# PLL.net
KiCad netlist of a schematic drawn in Altium Designer
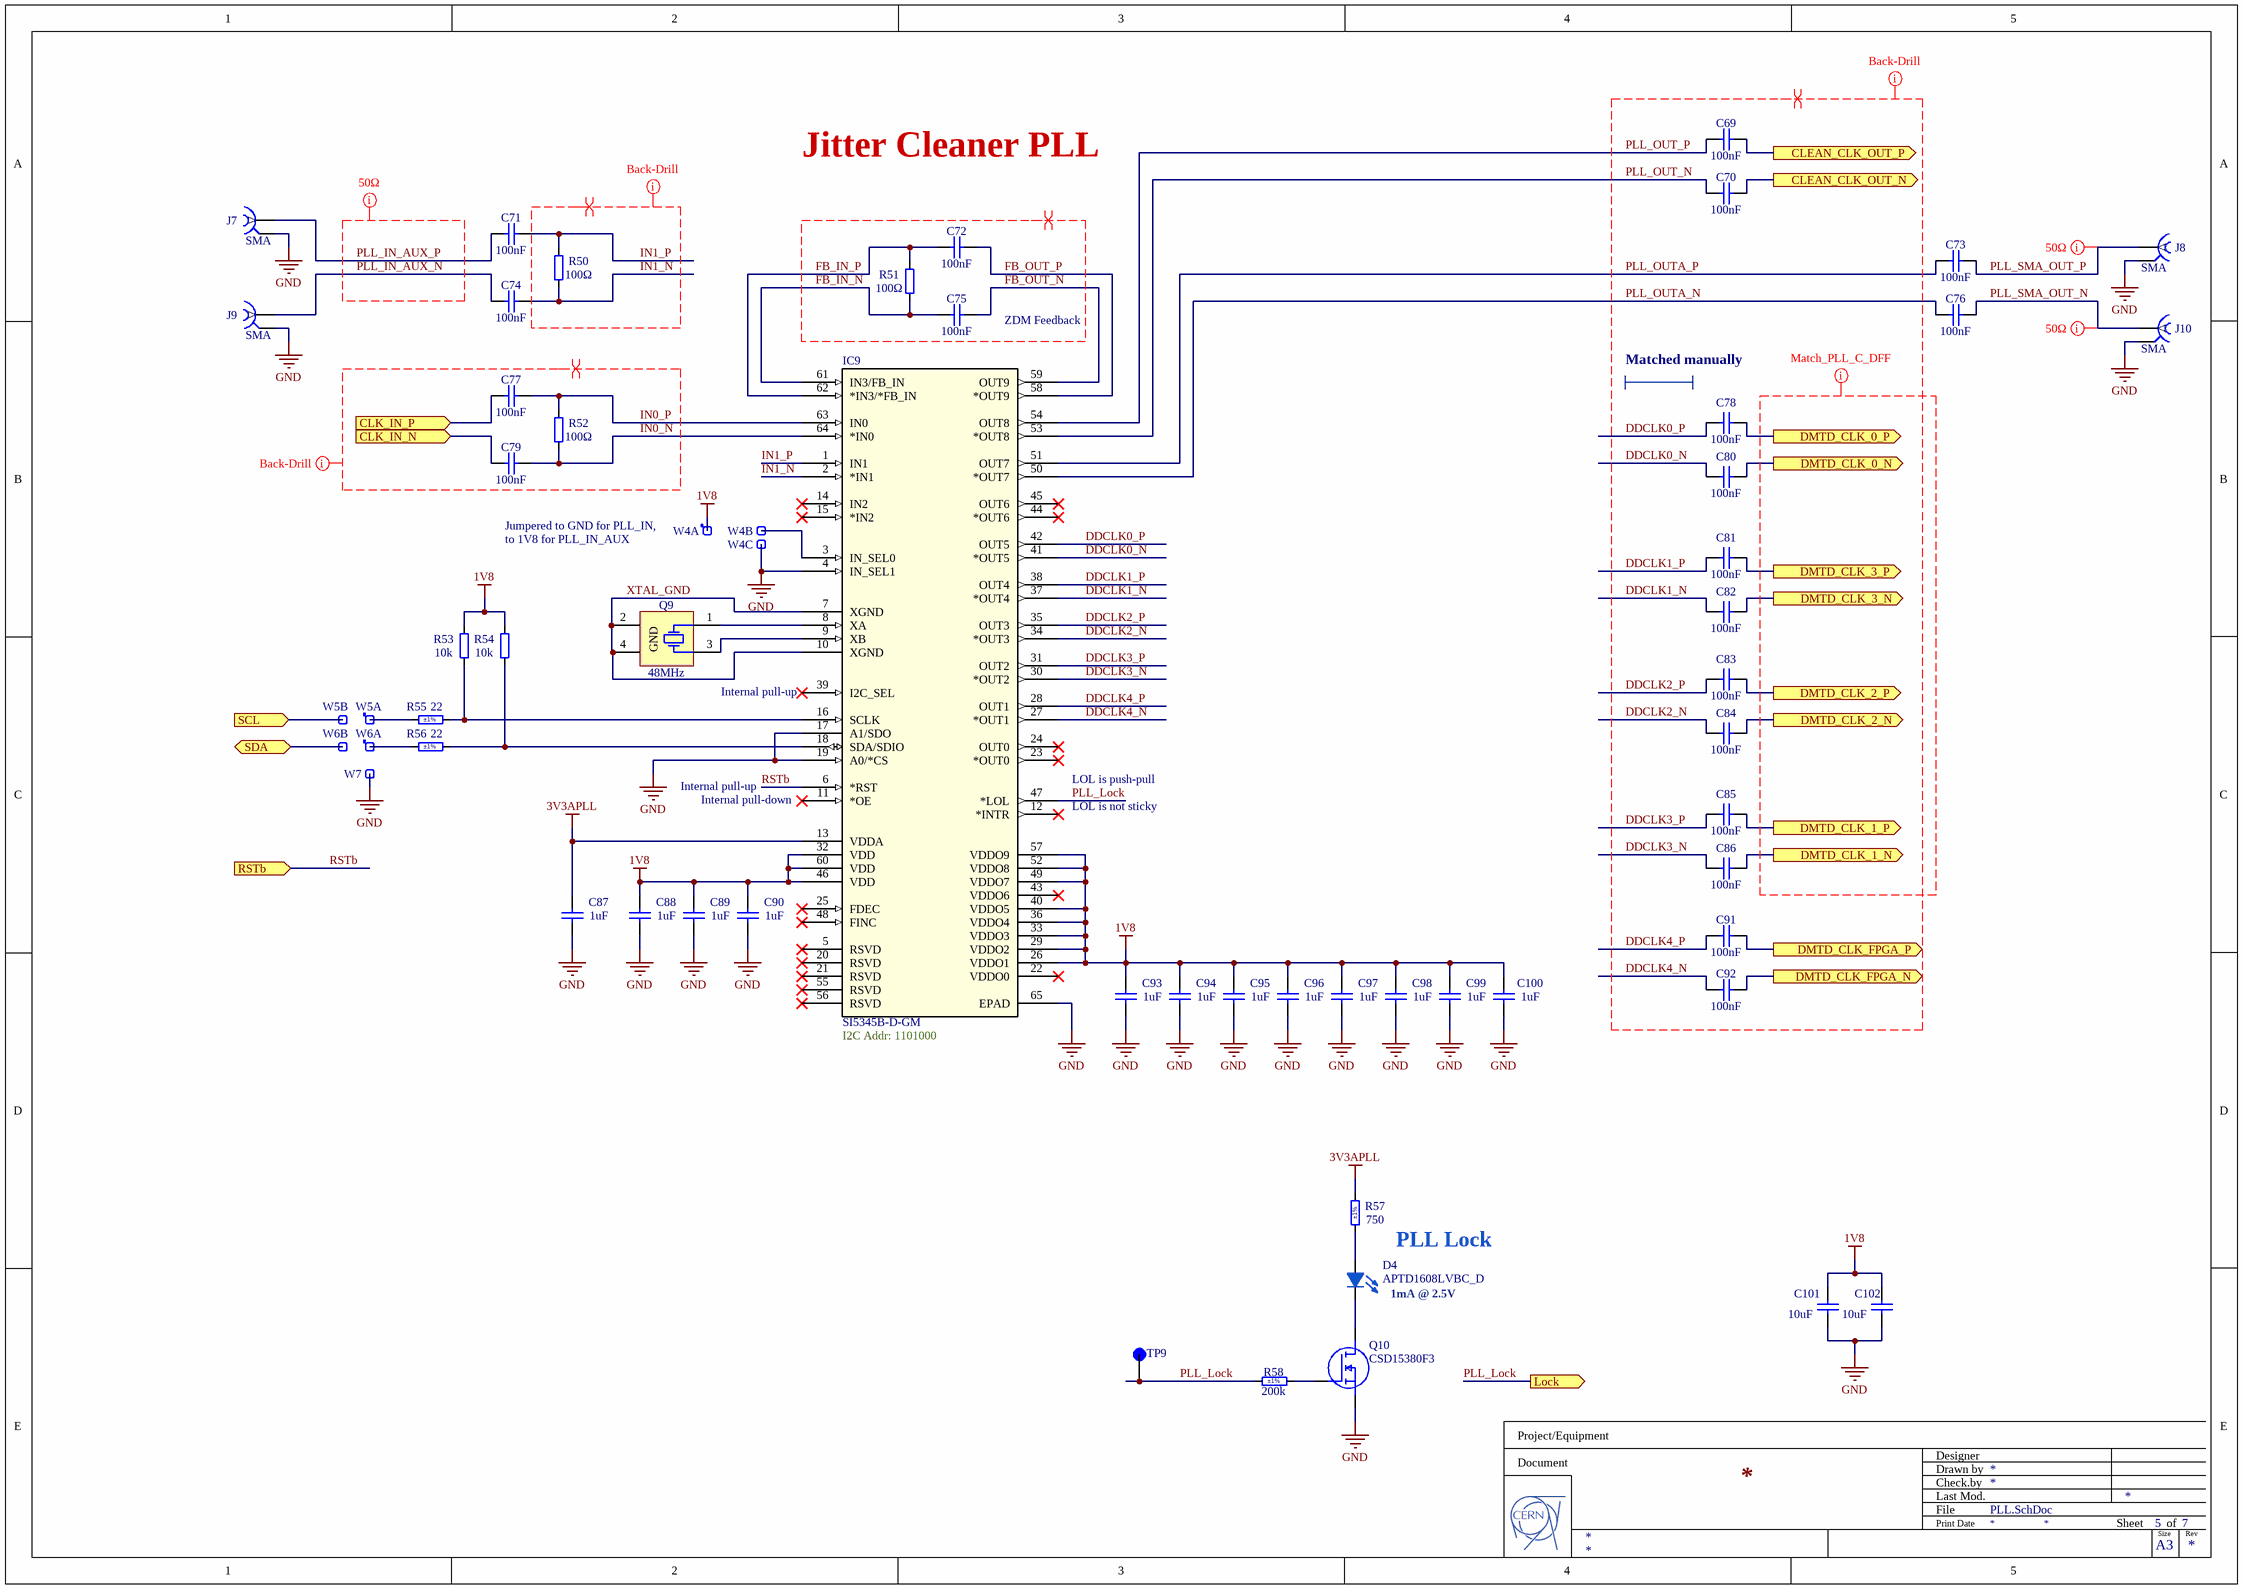
[diagram p0: PLL.SchDoc]

(export (version "E")
  (design (tool "Eeschema 10.0.6"))
  (components
    (comp (ref "C69")
      (value "100nF")
      (footprint "MURATA_HI_DENSITY_0201")
      (description "GRM033R61C104KE14")
      (libsource (lib "schLib") (part "C0201-100nF-high-density"))
    )
    (comp (ref "C70")
      (value "100nF")
      (footprint "MURATA_HI_DENSITY_0201")
      (description "GRM033R61C104KE14")
      (libsource (lib "schLib") (part "C0201-100nF-high-density"))
    )
    (comp (ref "C71")
      (value "100nF")
      (footprint "MURATA_HI_DENSITY_0201")
      (description "GRM033R61C104KE14")
      (libsource (lib "schLib") (part "C0201-100nF-high-density"))
    )
    (comp (ref "C72")
      (value "100nF")
      (footprint "MURATA_HI_DENSITY_0201")
      (description "GRM033R61C104KE14")
      (libsource (lib "schLib") (part "C0201-100nF-high-density"))
    )
    (comp (ref "C73")
      (value "100nF")
      (footprint "MURATA_HI_DENSITY_0201")
      (description "GRM033R61C104KE14")
      (libsource (lib "schLib") (part "C0201-100nF-high-density"))
    )
    (comp (ref "C74")
      (value "100nF")
      (footprint "MURATA_HI_DENSITY_0201")
      (description "GRM033R61C104KE14")
      (libsource (lib "schLib") (part "C0201-100nF-high-density"))
    )
    (comp (ref "C75")
      (value "100nF")
      (footprint "MURATA_HI_DENSITY_0201")
      (description "GRM033R61C104KE14")
      (libsource (lib "schLib") (part "C0201-100nF-high-density"))
    )
    (comp (ref "C76")
      (value "100nF")
      (footprint "MURATA_HI_DENSITY_0201")
      (description "GRM033R61C104KE14")
      (libsource (lib "schLib") (part "C0201-100nF-high-density"))
    )
    (comp (ref "C77")
      (value "100nF")
      (footprint "MURATA_HI_DENSITY_0201")
      (description "GRM033R61C104KE14")
      (libsource (lib "schLib") (part "C0201-100nF-high-density"))
    )
    (comp (ref "C78")
      (value "100nF")
      (footprint "MURATA_HI_DENSITY_0201")
      (description "GRM033R61C104KE14")
      (libsource (lib "schLib") (part "C0201-100nF-high-density"))
    )
    (comp (ref "C79")
      (value "100nF")
      (footprint "MURATA_HI_DENSITY_0201")
      (description "GRM033R61C104KE14")
      (libsource (lib "schLib") (part "C0201-100nF-high-density"))
    )
    (comp (ref "C80")
      (value "100nF")
      (footprint "MURATA_HI_DENSITY_0201")
      (description "GRM033R61C104KE14")
      (libsource (lib "schLib") (part "C0201-100nF-high-density"))
    )
    (comp (ref "C81")
      (value "100nF")
      (footprint "MURATA_HI_DENSITY_0201")
      (description "GRM033R61C104KE14")
      (libsource (lib "schLib") (part "C0201-100nF-high-density"))
    )
    (comp (ref "C82")
      (value "100nF")
      (footprint "MURATA_HI_DENSITY_0201")
      (description "GRM033R61C104KE14")
      (libsource (lib "schLib") (part "C0201-100nF-high-density"))
    )
    (comp (ref "C83")
      (value "100nF")
      (footprint "MURATA_HI_DENSITY_0201")
      (description "GRM033R61C104KE14")
      (libsource (lib "schLib") (part "C0201-100nF-high-density"))
    )
    (comp (ref "C84")
      (value "100nF")
      (footprint "MURATA_HI_DENSITY_0201")
      (description "GRM033R61C104KE14")
      (libsource (lib "schLib") (part "C0201-100nF-high-density"))
    )
    (comp (ref "C85")
      (value "100nF")
      (footprint "MURATA_HI_DENSITY_0201")
      (description "GRM033R61C104KE14")
      (libsource (lib "schLib") (part "C0201-100nF-high-density"))
    )
    (comp (ref "C86")
      (value "100nF")
      (footprint "MURATA_HI_DENSITY_0201")
      (description "GRM033R61C104KE14")
      (libsource (lib "schLib") (part "C0201-100nF-high-density"))
    )
    (comp (ref "C87")
      (value "1uF")
      (footprint "CAPC1005X55N")
      (description "GRM153B30J105ME15")
      (fields
        (field (name "PART NUMBER") "CC0402_1UF_16V_10%_X5R")
        (field (name "VOLTAGE") "16V")
        (field (name "AUTHOR") "CERN DEM JLC")
      )
      (libsource (lib "Capacitors") (part "Capacitor - non polarized"))
    )
    (comp (ref "C88")
      (value "1uF")
      (footprint "CAPC1005X55N")
      (description "GRM153B30J105ME15")
      (fields
        (field (name "PART NUMBER") "CC0402_1UF_16V_10%_X5R")
        (field (name "VOLTAGE") "16V")
        (field (name "AUTHOR") "CERN DEM JLC")
      )
      (libsource (lib "Capacitors") (part "Capacitor - non polarized"))
    )
    (comp (ref "C89")
      (value "1uF")
      (footprint "CAPC1005X55N")
      (description "GRM153B30J105ME15")
      (fields
        (field (name "PART NUMBER") "CC0402_1UF_16V_10%_X5R")
        (field (name "VOLTAGE") "16V")
        (field (name "AUTHOR") "CERN DEM JLC")
      )
      (libsource (lib "Capacitors") (part "Capacitor - non polarized"))
    )
    (comp (ref "C90")
      (value "1uF")
      (footprint "CAPC1005X55N")
      (description "GRM153B30J105ME15")
      (fields
        (field (name "PART NUMBER") "CC0402_1UF_16V_10%_X5R")
        (field (name "VOLTAGE") "16V")
        (field (name "AUTHOR") "CERN DEM JLC")
      )
      (libsource (lib "Capacitors") (part "Capacitor - non polarized"))
    )
    (comp (ref "C91")
      (value "100nF")
      (footprint "MURATA_HI_DENSITY_0201")
      (description "GRM033R61C104KE14")
      (libsource (lib "schLib") (part "C0201-100nF-high-density"))
    )
    (comp (ref "C92")
      (value "100nF")
      (footprint "MURATA_HI_DENSITY_0201")
      (description "GRM033R61C104KE14")
      (libsource (lib "schLib") (part "C0201-100nF-high-density"))
    )
    (comp (ref "C93")
      (value "1uF")
      (footprint "CAPC1005X55N")
      (description "GRM153B30J105ME15")
      (fields
        (field (name "PART NUMBER") "CC0402_1UF_16V_10%_X5R")
        (field (name "VOLTAGE") "16V")
        (field (name "AUTHOR") "CERN DEM JLC")
      )
      (libsource (lib "Capacitors") (part "Capacitor - non polarized"))
    )
    (comp (ref "C94")
      (value "1uF")
      (footprint "CAPC1005X55N")
      (description "GRM153B30J105ME15")
      (fields
        (field (name "PART NUMBER") "CC0402_1UF_16V_10%_X5R")
        (field (name "VOLTAGE") "16V")
        (field (name "AUTHOR") "CERN DEM JLC")
      )
      (libsource (lib "Capacitors") (part "Capacitor - non polarized"))
    )
    (comp (ref "C95")
      (value "1uF")
      (footprint "CAPC1005X55N")
      (description "GRM153B30J105ME15")
      (fields
        (field (name "PART NUMBER") "CC0402_1UF_16V_10%_X5R")
        (field (name "VOLTAGE") "16V")
        (field (name "AUTHOR") "CERN DEM JLC")
      )
      (libsource (lib "Capacitors") (part "Capacitor - non polarized"))
    )
    (comp (ref "C96")
      (value "1uF")
      (footprint "CAPC1005X55N")
      (description "GRM153B30J105ME15")
      (fields
        (field (name "PART NUMBER") "CC0402_1UF_16V_10%_X5R")
        (field (name "VOLTAGE") "16V")
        (field (name "AUTHOR") "CERN DEM JLC")
      )
      (libsource (lib "Capacitors") (part "Capacitor - non polarized"))
    )
    (comp (ref "C97")
      (value "1uF")
      (footprint "CAPC1005X55N")
      (description "GRM153B30J105ME15")
      (fields
        (field (name "PART NUMBER") "CC0402_1UF_16V_10%_X5R")
        (field (name "VOLTAGE") "16V")
        (field (name "AUTHOR") "CERN DEM JLC")
      )
      (libsource (lib "Capacitors") (part "Capacitor - non polarized"))
    )
    (comp (ref "C98")
      (value "1uF")
      (footprint "CAPC1005X55N")
      (description "GRM153B30J105ME15")
      (fields
        (field (name "PART NUMBER") "CC0402_1UF_16V_10%_X5R")
        (field (name "VOLTAGE") "16V")
        (field (name "AUTHOR") "CERN DEM JLC")
      )
      (libsource (lib "Capacitors") (part "Capacitor - non polarized"))
    )
    (comp (ref "C99")
      (value "1uF")
      (footprint "CAPC1005X55N")
      (description "GRM153B30J105ME15")
      (fields
        (field (name "PART NUMBER") "CC0402_1UF_16V_10%_X5R")
        (field (name "VOLTAGE") "16V")
        (field (name "AUTHOR") "CERN DEM JLC")
      )
      (libsource (lib "Capacitors") (part "Capacitor - non polarized"))
    )
    (comp (ref "C100")
      (value "1uF")
      (footprint "CAPC1005X55N")
      (description "GRM153B30J105ME15")
      (fields
        (field (name "PART NUMBER") "CC0402_1UF_16V_10%_X5R")
        (field (name "VOLTAGE") "16V")
        (field (name "AUTHOR") "CERN DEM JLC")
      )
      (libsource (lib "Capacitors") (part "Capacitor - non polarized"))
    )
    (comp (ref "C101")
      (value "10uF")
      (footprint "CAPC1608X87N")
      (description "C1608X5R1E106M080AC")
      (fields
        (field (name "PART NUMBER") "CC0603_10UF_6.3V_20%_X5R")
        (field (name "VOLTAGE") "6.3V")
        (field (name "AUTHOR") "CERN DEM JLC")
      )
      (libsource (lib "Capacitors") (part "Capacitor - non polarized"))
    )
    (comp (ref "C102")
      (value "10uF")
      (footprint "CAPC1608X87N")
      (description "C1608X5R1E106M080AC")
      (fields
        (field (name "PART NUMBER") "CC0603_10UF_6.3V_20%_X5R")
        (field (name "VOLTAGE") "6.3V")
        (field (name "AUTHOR") "CERN DEM JLC")
      )
      (libsource (lib "Capacitors") (part "Capacitor - non polarized"))
    )
    (comp (ref "D4")
      (value "APTD1608LVBC_D")
      (footprint "SamacSys:LEDC1608X110N")
      (description "LED")
      (fields
        (field (name "MANUFACTURER_PART_NUMBER") "APTD1608LVBC/D")
        (field (name "MOUSER PART NUMBER") "604-APTD1608LVBCD")
      )
      (libsource (lib "SamacSys") (part "APTD1608LVBC_D"))
    )
    (comp (ref "IC9")
      (value "SI5345B-D-GM")
      (footprint "SamacSys:QFN50P900X900X90-65N-D")
      (description "Integrated Circuit")
      (fields (field (name "MOUSER PART NUMBER") "634-SI5345B-D-GM"))
      (libsource (lib "SamacSys") (part "SI5345B-D-GM"))
    )
    (comp (ref "J7")
      (value "SMA")
      (footprint "SAMTEC_SMA-J-P-H-ST-MT1")
      (fields
        (field (name "PART NUMBER") "SAMTEC_SMA-J-P-H-ST-MT1")
        (field (name "MANUFACTURER") "SAMTEC")
        (field (name "MANUFACTURER PART NUMBER") "SMA-J-P-H-ST-MT1")
        (field (name "AUTHOR") "CERN DEM HF")
      )
      (libsource (lib "Connectors") (part "Coax_1Female_1Shield"))
    )
    (comp (ref "J8")
      (value "SMA")
      (footprint "SAMTEC_SMA-J-P-H-ST-MT1")
      (fields
        (field (name "PART NUMBER") "SAMTEC_SMA-J-P-H-ST-MT1")
        (field (name "MANUFACTURER") "SAMTEC")
        (field (name "MANUFACTURER PART NUMBER") "SMA-J-P-H-ST-MT1")
        (field (name "AUTHOR") "CERN DEM HF")
      )
      (libsource (lib "") (part "Coax_1Female_1Shield_1"))
    )
    (comp (ref "J9")
      (value "SMA")
      (footprint "SAMTEC_SMA-J-P-H-ST-MT1")
      (fields
        (field (name "PART NUMBER") "SAMTEC_SMA-J-P-H-ST-MT1")
        (field (name "MANUFACTURER") "SAMTEC")
        (field (name "MANUFACTURER PART NUMBER") "SMA-J-P-H-ST-MT1")
        (field (name "AUTHOR") "CERN DEM HF")
      )
      (libsource (lib "Connectors") (part "Coax_1Female_1Shield"))
    )
    (comp (ref "J10")
      (value "SMA")
      (footprint "SAMTEC_SMA-J-P-H-ST-MT1")
      (fields
        (field (name "PART NUMBER") "SAMTEC_SMA-J-P-H-ST-MT1")
        (field (name "MANUFACTURER") "SAMTEC")
        (field (name "MANUFACTURER PART NUMBER") "SMA-J-P-H-ST-MT1")
        (field (name "AUTHOR") "CERN DEM HF")
      )
      (libsource (lib "") (part "Coax_1Female_1Shield_1"))
    )
    (comp (ref "Q9")
      (value "48MHz")
      (footprint "XTAL_KYOCERA_CX3225SB")
      (description "Crystal 4 pins 1=XTAL Control 2=GND3=XTAL 4=GND")
      (fields
        (field (name "PART NUMBER") "XTAL_48MHZ_KYOCERA_CX3225SB48000D0FPJC1")
        (field (name "MANUFACTURER") "KYOCERA")
        (field (name "AUTHOR") "CERN DEM JLC")
      )
      (libsource (lib "ICs And Semiconductors") (part "Quartz Crystal 1X 2GND 3X 4GND"))
    )
    (comp (ref "Q10")
      (value "CSD15380F3")
      (footprint "SamacSys:CSD15380F3")
      (description "MOSFET (N-Channel)")
      (fields (field (name "MOUSER PART NUMBER") "595-CSD15380F3"))
      (libsource (lib "*") (part "CSD15380F3"))
    )
    (comp (ref "R50")
      (value "100Ω")
      (footprint "MURATA_HI_DENSITY_0201")
      (description "Resistor")
      (libsource (lib "schLib") (part "R0201-100ohm-high-density"))
    )
    (comp (ref "R51")
      (value "100Ω")
      (footprint "MURATA_HI_DENSITY_0201")
      (description "Resistor")
      (libsource (lib "schLib") (part "R0201-100ohm-high-density"))
    )
    (comp (ref "R52")
      (value "100Ω")
      (footprint "MURATA_HI_DENSITY_0201")
      (description "Resistor")
      (libsource (lib "schLib") (part "R0201-100ohm-high-density"))
    )
    (comp (ref "R53")
      (value "10k")
      (footprint "MURATA_HI_DENSITY_0201")
      (description "Resistor 10k")
      (libsource (lib "schLib") (part "R0201-100ohm-high-density"))
    )
    (comp (ref "R54")
      (value "10k")
      (footprint "MURATA_HI_DENSITY_0201")
      (description "Resistor 10k")
      (libsource (lib "schLib") (part "R0201-100ohm-high-density"))
    )
    (comp (ref "R55")
      (value "22")
      (footprint "RESC1005X40N")
      (description "Resistor - 1%")
      (fields
        (field (name "TOLERANCE") "±1%")
        (field (name "PART NUMBER") "R0402_22R_1%_0.0625W_100PPM")
        (field (name "POWER") "0.0625W")
        (field (name "AUTHOR") "CERN DEM JLC")
      )
      (libsource (lib "Resistors") (part "Resistor - 1%"))
    )
    (comp (ref "R56")
      (value "22")
      (footprint "RESC1005X40N")
      (description "Resistor - 1%")
      (fields
        (field (name "TOLERANCE") "±1%")
        (field (name "PART NUMBER") "R0402_22R_1%_0.0625W_100PPM")
        (field (name "POWER") "0.0625W")
        (field (name "AUTHOR") "CERN DEM JLC")
      )
      (libsource (lib "Resistors") (part "Resistor - 1%"))
    )
    (comp (ref "R57")
      (value "750")
      (footprint "RESC1005X40N")
      (description "Resistor - 1%")
      (fields
        (field (name "TOLERANCE") "±1%")
        (field (name "PART NUMBER") "R0402_750R_1%_0.0625W_100PPM")
        (field (name "POWER") "0.0625W")
        (field (name "AUTHOR") "CERN DEM JLC")
      )
      (libsource (lib "Resistors") (part "Resistor - 1%"))
    )
    (comp (ref "R58")
      (value "200k")
      (footprint "RESC1005X40N")
      (description "Resistor - 1%")
      (fields
        (field (name "TOLERANCE") "±1%")
        (field (name "PART NUMBER") "R0402_200K_1%_0.0625W_100PPM")
        (field (name "POWER") "0.0625W")
        (field (name "AUTHOR") "CERN DEM JLC")
      )
      (libsource (lib "Resistors") (part "Resistor - 1%"))
    )
    (comp (ref "TP9")
      (value "RCU-0C")
      (footprint "TP+195X110")
      (fields (field (name "MF") "{'manufacturer': u'TE Connectivity AMP Connectors'}"))
      (libsource (lib "RCU-0C") (part "RCU-0C"))
    )
    (comp (ref "W4")
      (value "Header 3")
      (footprint "SAMTEC_HTSW-103-23-L-S")
      (description "3 Mini Wire-Wrap Contact Strip Header")
      (fields
        (field (name "PART NUMBER") "SAMTEC_HTSW-103-23-L-S")
        (field (name "MANUFACTURER") "SAMTEC")
        (field (name "AUTHOR") "CERN DEM JLC")
      )
      (libsource (lib "Connectors") (part "Wire-Wrap Contact x3"))
    )
    (comp (ref "W5")
      (value "Header 2")
      (footprint "SAMTEC_HTSW-102-23-L-S")
      (description "2 Mini Wire-Wrap Contact Strip Header")
      (fields
        (field (name "PART NUMBER") "SAMTEC_HTSW-102-23-L-S")
        (field (name "MANUFACTURER") "SAMTEC")
        (field (name "AUTHOR") "CERN DEM JLC")
      )
      (libsource (lib "Connectors") (part "Wire-Wrap Contact x2"))
    )
    (comp (ref "W6")
      (value "Header 2")
      (footprint "SAMTEC_HTSW-102-23-L-S")
      (description "2 Mini Wire-Wrap Contact Strip Header")
      (fields
        (field (name "PART NUMBER") "SAMTEC_HTSW-102-23-L-S")
        (field (name "MANUFACTURER") "SAMTEC")
        (field (name "AUTHOR") "CERN DEM JLC")
      )
      (libsource (lib "Connectors") (part "Wire-Wrap Contact x2"))
    )
    (comp (ref "W7")
      (value "Header 1")
      (footprint "SAMTEC_HTSW-101-23-L-S")
      (description "Single Mini Wire-Wrap Contact")
      (fields
        (field (name "PART NUMBER") "SAMTEC_HTSW-101-23-L-S")
        (field (name "MANUFACTURER") "SAMTEC")
        (field (name "AUTHOR") "CERN DEM JLC")
      )
      (libsource (lib "Connectors") (part "Wire-Wrap Contact"))
    )
  )
  (nets
    (net (code "1") (name "/CLEAN_CLK_OUT_N") (class "Default")
      (node (ref "C70") (pin "2") (pinfunction "2_2") (pintype "passive"))
    )
    (net (code "2") (name "/CLEAN_CLK_OUT_P") (class "Default")
      (node (ref "C69") (pin "2") (pinfunction "2_2") (pintype "passive"))
    )
    (net (code "3") (name "/CLK_IN_N") (class "Default")
      (node (ref "C79") (pin "2") (pinfunction "2_2") (pintype "passive"))
    )
    (net (code "4") (name "/CLK_IN_P") (class "Default")
      (node (ref "C77") (pin "2") (pinfunction "2_2") (pintype "passive"))
    )
    (net (code "5") (name "/DDCLK0_N") (class "Default")
      (node (ref "C80") (pin "1") (pinfunction "1_1") (pintype "passive"))
      (node (ref "IC9") (pin "41") (pinfunction "*OUT5_41") (pintype "output"))
    )
    (net (code "6") (name "/DDCLK0_P") (class "Default")
      (node (ref "C78") (pin "1") (pinfunction "1_1") (pintype "passive"))
      (node (ref "IC9") (pin "42") (pinfunction "OUT5_42") (pintype "output"))
    )
    (net (code "7") (name "/DDCLK1_N") (class "Default")
      (node (ref "C82") (pin "1") (pinfunction "1_1") (pintype "passive"))
      (node (ref "IC9") (pin "37") (pinfunction "*OUT4_37") (pintype "output"))
    )
    (net (code "8") (name "/DDCLK1_P") (class "Default")
      (node (ref "C81") (pin "1") (pinfunction "1_1") (pintype "passive"))
      (node (ref "IC9") (pin "38") (pinfunction "OUT4_38") (pintype "output"))
    )
    (net (code "9") (name "/DDCLK2_N") (class "Default")
      (node (ref "C84") (pin "1") (pinfunction "1_1") (pintype "passive"))
      (node (ref "IC9") (pin "34") (pinfunction "*OUT3_34") (pintype "output"))
    )
    (net (code "10") (name "/DDCLK2_P") (class "Default")
      (node (ref "C83") (pin "1") (pinfunction "1_1") (pintype "passive"))
      (node (ref "IC9") (pin "35") (pinfunction "OUT3_35") (pintype "output"))
    )
    (net (code "11") (name "/DDCLK3_N") (class "Default")
      (node (ref "C86") (pin "1") (pinfunction "1_1") (pintype "passive"))
      (node (ref "IC9") (pin "30") (pinfunction "*OUT2_30") (pintype "output"))
    )
    (net (code "12") (name "/DDCLK3_P") (class "Default")
      (node (ref "C85") (pin "1") (pinfunction "1_1") (pintype "passive"))
      (node (ref "IC9") (pin "31") (pinfunction "OUT2_31") (pintype "output"))
    )
    (net (code "13") (name "/DDCLK4_N") (class "Default")
      (node (ref "C92") (pin "1") (pinfunction "1_1") (pintype "passive"))
      (node (ref "IC9") (pin "27") (pinfunction "*OUT1_27") (pintype "output"))
    )
    (net (code "14") (name "/DDCLK4_P") (class "Default")
      (node (ref "C91") (pin "1") (pinfunction "1_1") (pintype "passive"))
      (node (ref "IC9") (pin "28") (pinfunction "OUT1_28") (pintype "output"))
    )
    (net (code "15") (name "/DMTD_CLK_0_N") (class "Default")
      (node (ref "C80") (pin "2") (pinfunction "2_2") (pintype "passive"))
    )
    (net (code "16") (name "/DMTD_CLK_0_P") (class "Default")
      (node (ref "C78") (pin "2") (pinfunction "2_2") (pintype "passive"))
    )
    (net (code "17") (name "/DMTD_CLK_1_N") (class "Default")
      (node (ref "C86") (pin "2") (pinfunction "2_2") (pintype "passive"))
    )
    (net (code "18") (name "/DMTD_CLK_1_P") (class "Default")
      (node (ref "C85") (pin "2") (pinfunction "2_2") (pintype "passive"))
    )
    (net (code "19") (name "/DMTD_CLK_2_N") (class "Default")
      (node (ref "C84") (pin "2") (pinfunction "2_2") (pintype "passive"))
    )
    (net (code "20") (name "/DMTD_CLK_2_P") (class "Default")
      (node (ref "C83") (pin "2") (pinfunction "2_2") (pintype "passive"))
    )
    (net (code "21") (name "/DMTD_CLK_3_N") (class "Default")
      (node (ref "C82") (pin "2") (pinfunction "2_2") (pintype "passive"))
    )
    (net (code "22") (name "/DMTD_CLK_3_P") (class "Default")
      (node (ref "C81") (pin "2") (pinfunction "2_2") (pintype "passive"))
    )
    (net (code "23") (name "/DMTD_CLK_FPGA_N") (class "Default")
      (node (ref "C92") (pin "2") (pinfunction "2_2") (pintype "passive"))
    )
    (net (code "24") (name "/DMTD_CLK_FPGA_P") (class "Default")
      (node (ref "C91") (pin "2") (pinfunction "2_2") (pintype "passive"))
    )
    (net (code "25") (name "/FB_IN_N") (class "Default")
      (node (ref "C75") (pin "1") (pinfunction "1_1") (pintype "passive"))
      (node (ref "IC9") (pin "61") (pinfunction "IN3/FB_IN_61") (pintype "input"))
      (node (ref "R51") (pin "1") (pinfunction "1_1") (pintype "passive"))
    )
    (net (code "26") (name "/FB_IN_P") (class "Default")
      (node (ref "C72") (pin "1") (pinfunction "1_1") (pintype "passive"))
      (node (ref "IC9") (pin "62") (pinfunction "*IN3/*FB_IN_62") (pintype "input"))
      (node (ref "R51") (pin "2") (pinfunction "2_2") (pintype "passive"))
    )
    (net (code "27") (name "/FB_OUT_N") (class "Default")
      (node (ref "C75") (pin "2") (pinfunction "2_2") (pintype "passive"))
      (node (ref "IC9") (pin "59") (pinfunction "OUT9_59") (pintype "output"))
    )
    (net (code "28") (name "/FB_OUT_P") (class "Default")
      (node (ref "C72") (pin "2") (pinfunction "2_2") (pintype "passive"))
      (node (ref "IC9") (pin "58") (pinfunction "*OUT9_58") (pintype "output"))
    )
    (net (code "29") (name "/IN0_N") (class "Default")
      (node (ref "C79") (pin "1") (pinfunction "1_1") (pintype "passive"))
      (node (ref "IC9") (pin "64") (pinfunction "*IN0_64") (pintype "input"))
      (node (ref "R52") (pin "1") (pinfunction "1_1") (pintype "passive"))
    )
    (net (code "30") (name "/IN0_P") (class "Default")
      (node (ref "C77") (pin "1") (pinfunction "1_1") (pintype "passive"))
      (node (ref "IC9") (pin "63") (pinfunction "IN0_63") (pintype "input"))
      (node (ref "R52") (pin "2") (pinfunction "2_2") (pintype "passive"))
    )
    (net (code "31") (name "/IN1_N") (class "Default")
      (node (ref "C74") (pin "1") (pinfunction "1_1") (pintype "passive"))
      (node (ref "IC9") (pin "2") (pinfunction "*IN1_2") (pintype "input"))
      (node (ref "R50") (pin "1") (pinfunction "1_1") (pintype "passive"))
    )
    (net (code "32") (name "/IN1_P") (class "Default")
      (node (ref "C71") (pin "1") (pinfunction "1_1") (pintype "passive"))
      (node (ref "IC9") (pin "1") (pinfunction "IN1_1") (pintype "input"))
      (node (ref "R50") (pin "2") (pinfunction "2_2") (pintype "passive"))
    )
    (net (code "33") (name "/PLL_IN_AUX_N") (class "Default")
      (node (ref "C74") (pin "2") (pinfunction "2_2") (pintype "passive"))
      (node (ref "J9") (pin "1") (pinfunction "1_1") (pintype "output"))
    )
    (net (code "34") (name "/PLL_IN_AUX_P") (class "Default")
      (node (ref "C71") (pin "2") (pinfunction "2_2") (pintype "passive"))
      (node (ref "J7") (pin "1") (pinfunction "1_1") (pintype "output"))
    )
    (net (code "35") (name "/PLL_Lock") (class "Default")
      (node (ref "IC9") (pin "47") (pinfunction "*LOL_47") (pintype "output"))
      (node (ref "R58") (pin "1") (pinfunction "1_1") (pintype "passive"))
      (node (ref "TP9") (pin "1") (pinfunction "TP_1") (pintype "passive"))
    )
    (net (code "36") (name "/PLL_OUTA_N") (class "Default")
      (node (ref "C76") (pin "1") (pinfunction "1_1") (pintype "passive"))
      (node (ref "IC9") (pin "50") (pinfunction "*OUT7_50") (pintype "output"))
    )
    (net (code "37") (name "/PLL_OUTA_P") (class "Default")
      (node (ref "C73") (pin "1") (pinfunction "1_1") (pintype "passive"))
      (node (ref "IC9") (pin "51") (pinfunction "OUT7_51") (pintype "output"))
    )
    (net (code "38") (name "/PLL_OUT_N") (class "Default")
      (node (ref "C70") (pin "1") (pinfunction "1_1") (pintype "passive"))
      (node (ref "IC9") (pin "53") (pinfunction "*OUT8_53") (pintype "output"))
    )
    (net (code "39") (name "/PLL_OUT_P") (class "Default")
      (node (ref "C69") (pin "1") (pinfunction "1_1") (pintype "passive"))
      (node (ref "IC9") (pin "54") (pinfunction "OUT8_54") (pintype "output"))
    )
    (net (code "40") (name "/PLL_SMA_OUT_N") (class "Default")
      (node (ref "C76") (pin "2") (pinfunction "2_2") (pintype "passive"))
      (node (ref "J10") (pin "1") (pinfunction "1_1") (pintype "output"))
    )
    (net (code "41") (name "/PLL_SMA_OUT_P") (class "Default")
      (node (ref "C73") (pin "2") (pinfunction "2_2") (pintype "passive"))
      (node (ref "J8") (pin "1") (pinfunction "1_1") (pintype "output"))
    )
    (net (code "42") (name "/RSTb") (class "Default")
      (node (ref "IC9") (pin "6") (pinfunction "*RST_6") (pintype "input"))
    )
    (net (code "43") (name "/SCL") (class "Default")
      (node (ref "W5") (pin "2") (pinfunction "2_2") (pintype "passive"))
    )
    (net (code "44") (name "/SDA") (class "Default")
      (node (ref "W6") (pin "2") (pinfunction "2_2") (pintype "passive"))
    )
    (net (code "45") (name "/XTAL_GND") (class "Default")
      (node (ref "IC9") (pin "10") (pinfunction "XGND_10") (pintype "power_in"))
      (node (ref "IC9") (pin "7") (pinfunction "XGND_7") (pintype "power_in"))
      (node (ref "Q9") (pin "2") (pinfunction "GND_2") (pintype "power_in"))
      (node (ref "Q9") (pin "4") (pinfunction "GND_4") (pintype "power_in"))
    )
    (net (code "46") (name "1V8") (class "Default")
      (node (ref "C100") (pin "2") (pinfunction "2_2") (pintype "passive"))
      (node (ref "C101") (pin "2") (pinfunction "2_2") (pintype "passive"))
      (node (ref "C102") (pin "2") (pinfunction "2_2") (pintype "passive"))
      (node (ref "C88") (pin "2") (pinfunction "2_2") (pintype "passive"))
      (node (ref "C89") (pin "2") (pinfunction "2_2") (pintype "passive"))
      (node (ref "C90") (pin "2") (pinfunction "2_2") (pintype "passive"))
      (node (ref "C93") (pin "2") (pinfunction "2_2") (pintype "passive"))
      (node (ref "C94") (pin "2") (pinfunction "2_2") (pintype "passive"))
      (node (ref "C95") (pin "2") (pinfunction "2_2") (pintype "passive"))
      (node (ref "C96") (pin "2") (pinfunction "2_2") (pintype "passive"))
      (node (ref "C97") (pin "2") (pinfunction "2_2") (pintype "passive"))
      (node (ref "C98") (pin "2") (pinfunction "2_2") (pintype "passive"))
      (node (ref "C99") (pin "2") (pinfunction "2_2") (pintype "passive"))
      (node (ref "IC9") (pin "26") (pinfunction "VDDO1_26") (pintype "power_in"))
      (node (ref "IC9") (pin "29") (pinfunction "VDDO2_29") (pintype "power_in"))
      (node (ref "IC9") (pin "32") (pinfunction "VDD_32") (pintype "power_in"))
      (node (ref "IC9") (pin "33") (pinfunction "VDDO3_33") (pintype "power_in"))
      (node (ref "IC9") (pin "36") (pinfunction "VDDO4_36") (pintype "power_in"))
      (node (ref "IC9") (pin "40") (pinfunction "VDDO5_40") (pintype "power_in"))
      (node (ref "IC9") (pin "46") (pinfunction "VDD_46") (pintype "power_in"))
      (node (ref "IC9") (pin "49") (pinfunction "VDDO7_49") (pintype "power_in"))
      (node (ref "IC9") (pin "52") (pinfunction "VDDO8_52") (pintype "power_in"))
      (node (ref "IC9") (pin "57") (pinfunction "VDDO9_57") (pintype "power_in"))
      (node (ref "IC9") (pin "60") (pinfunction "VDD_60") (pintype "power_in"))
      (node (ref "R53") (pin "2") (pinfunction "2_2") (pintype "passive"))
      (node (ref "R54") (pin "2") (pinfunction "2_2") (pintype "passive"))
      (node (ref "W4") (pin "1") (pinfunction "1_1") (pintype "passive"))
    )
    (net (code "47") (name "3V3APLL") (class "Default")
      (node (ref "C87") (pin "2") (pinfunction "2_2") (pintype "passive"))
      (node (ref "IC9") (pin "13") (pinfunction "VDDA_13") (pintype "power_in"))
      (node (ref "R57") (pin "2") (pinfunction "2_2") (pintype "passive"))
    )
    (net (code "48") (name "GND") (class "Default")
      (node (ref "C100") (pin "1") (pinfunction "1_1") (pintype "passive"))
      (node (ref "C101") (pin "1") (pinfunction "1_1") (pintype "passive"))
      (node (ref "C102") (pin "1") (pinfunction "1_1") (pintype "passive"))
      (node (ref "C87") (pin "1") (pinfunction "1_1") (pintype "passive"))
      (node (ref "C88") (pin "1") (pinfunction "1_1") (pintype "passive"))
      (node (ref "C89") (pin "1") (pinfunction "1_1") (pintype "passive"))
      (node (ref "C90") (pin "1") (pinfunction "1_1") (pintype "passive"))
      (node (ref "C93") (pin "1") (pinfunction "1_1") (pintype "passive"))
      (node (ref "C94") (pin "1") (pinfunction "1_1") (pintype "passive"))
      (node (ref "C95") (pin "1") (pinfunction "1_1") (pintype "passive"))
      (node (ref "C96") (pin "1") (pinfunction "1_1") (pintype "passive"))
      (node (ref "C97") (pin "1") (pinfunction "1_1") (pintype "passive"))
      (node (ref "C98") (pin "1") (pinfunction "1_1") (pintype "passive"))
      (node (ref "C99") (pin "1") (pinfunction "1_1") (pintype "passive"))
      (node (ref "IC9") (pin "17") (pinfunction "A1/SDO_17") (pintype "passive"))
      (node (ref "IC9") (pin "19") (pinfunction "A0/*CS_19") (pintype "input"))
      (node (ref "IC9") (pin "4") (pinfunction "IN_SEL1_4") (pintype "input"))
      (node (ref "IC9") (pin "65") (pinfunction "EPAD_65") (pintype "passive"))
      (node (ref "J10") (pin "2") (pinfunction "2_2") (pintype "power_in"))
      (node (ref "J7") (pin "2") (pinfunction "2_2") (pintype "power_in"))
      (node (ref "J8") (pin "2") (pinfunction "2_2") (pintype "power_in"))
      (node (ref "J9") (pin "2") (pinfunction "2_2") (pintype "power_in"))
      (node (ref "Q10") (pin "2") (pinfunction "S_2") (pintype "passive"))
      (node (ref "W4") (pin "3") (pinfunction "3_3") (pintype "bidirectional"))
      (node (ref "W7") (pin "1") (pinfunction "1_1") (pintype "passive"))
    )
    (net (code "49") (name "Net-(D4-A)") (class "Default")
      (node (ref "D4") (pin "2") (pinfunction "A_2") (pintype "passive"))
      (node (ref "R57") (pin "1") (pinfunction "1_1") (pintype "passive"))
    )
    (net (code "50") (name "Net-(D4-K)") (class "Default")
      (node (ref "D4") (pin "1") (pinfunction "K_1") (pintype "passive"))
      (node (ref "Q10") (pin "3") (pinfunction "D_3") (pintype "passive"))
    )
    (net (code "51") (name "Net-(IC9-IN_SEL0)") (class "Default")
      (node (ref "IC9") (pin "3") (pinfunction "IN_SEL0_3") (pintype "input"))
      (node (ref "W4") (pin "2") (pinfunction "2_2") (pintype "bidirectional"))
    )
    (net (code "52") (name "Net-(IC9-SCLK)") (class "Default")
      (node (ref "IC9") (pin "16") (pinfunction "SCLK_16") (pintype "input"))
      (node (ref "R53") (pin "1") (pinfunction "1_1") (pintype "passive"))
      (node (ref "R55") (pin "2") (pinfunction "2_2") (pintype "passive"))
    )
    (net (code "53") (name "Net-(IC9-SDA{slash}SDIO)") (class "Default")
      (node (ref "IC9") (pin "18") (pinfunction "SDA/SDIO_18") (pintype "bidirectional"))
      (node (ref "R54") (pin "1") (pinfunction "1_1") (pintype "passive"))
      (node (ref "R56") (pin "2") (pinfunction "2_2") (pintype "passive"))
    )
    (net (code "54") (name "Net-(IC9-XA)") (class "Default")
      (node (ref "IC9") (pin "8") (pinfunction "XA_8") (pintype "input"))
      (node (ref "Q9") (pin "1") (pinfunction "X_1") (pintype "passive"))
    )
    (net (code "55") (name "Net-(IC9-XB)") (class "Default")
      (node (ref "IC9") (pin "9") (pinfunction "XB_9") (pintype "input"))
      (node (ref "Q9") (pin "3") (pinfunction "X_3") (pintype "passive"))
    )
    (net (code "56") (name "Net-(Q10-G)") (class "Default")
      (node (ref "Q10") (pin "1") (pinfunction "G_1") (pintype "passive"))
      (node (ref "R58") (pin "2") (pinfunction "2_2") (pintype "passive"))
    )
    (net (code "57") (name "Net-(R55-Pad1)") (class "Default")
      (node (ref "R55") (pin "1") (pinfunction "1_1") (pintype "passive"))
      (node (ref "W5") (pin "1") (pinfunction "1_1") (pintype "bidirectional"))
    )
    (net (code "58") (name "Net-(R56-Pad1)") (class "Default")
      (node (ref "R56") (pin "1") (pinfunction "1_1") (pintype "passive"))
      (node (ref "W6") (pin "1") (pinfunction "1_1") (pintype "bidirectional"))
    )
    (net (code "59") (name "unconnected-(IC9-*IN2-Pad15)") (class "Default")
      (node (ref "IC9") (pin "15") (pinfunction "*IN2_15") (pintype "input+no_connect"))
    )
    (net (code "60") (name "unconnected-(IC9-*INTR-Pad12)") (class "Default")
      (node (ref "IC9") (pin "12") (pinfunction "*INTR_12") (pintype "output+no_connect"))
    )
    (net (code "61") (name "unconnected-(IC9-*OE-Pad11)") (class "Default")
      (node (ref "IC9") (pin "11") (pinfunction "*OE_11") (pintype "input+no_connect"))
    )
    (net (code "62") (name "unconnected-(IC9-*OUT0-Pad23)") (class "Default")
      (node (ref "IC9") (pin "23") (pinfunction "*OUT0_23") (pintype "output+no_connect"))
    )
    (net (code "63") (name "unconnected-(IC9-*OUT6-Pad44)") (class "Default")
      (node (ref "IC9") (pin "44") (pinfunction "*OUT6_44") (pintype "output+no_connect"))
    )
    (net (code "64") (name "unconnected-(IC9-FDEC-Pad25)") (class "Default")
      (node (ref "IC9") (pin "25") (pinfunction "FDEC_25") (pintype "input+no_connect"))
    )
    (net (code "65") (name "unconnected-(IC9-FINC-Pad48)") (class "Default")
      (node (ref "IC9") (pin "48") (pinfunction "FINC_48") (pintype "input+no_connect"))
    )
    (net (code "66") (name "unconnected-(IC9-I2C_SEL-Pad39)") (class "Default")
      (node (ref "IC9") (pin "39") (pinfunction "I2C_SEL_39") (pintype "input+no_connect"))
    )
    (net (code "67") (name "unconnected-(IC9-IN2-Pad14)") (class "Default")
      (node (ref "IC9") (pin "14") (pinfunction "IN2_14") (pintype "input+no_connect"))
    )
    (net (code "68") (name "unconnected-(IC9-OUT0-Pad24)") (class "Default")
      (node (ref "IC9") (pin "24") (pinfunction "OUT0_24") (pintype "output+no_connect"))
    )
    (net (code "69") (name "unconnected-(IC9-OUT6-Pad45)") (class "Default")
      (node (ref "IC9") (pin "45") (pinfunction "OUT6_45") (pintype "output+no_connect"))
    )
    (net (code "70") (name "unconnected-(IC9-RSVD-Pad5)") (class "Default")
      (node (ref "IC9") (pin "5") (pinfunction "RSVD_5") (pintype "passive+no_connect"))
    )
    (net (code "71") (name "unconnected-(IC9-RSVD-Pad20)") (class "Default")
      (node (ref "IC9") (pin "20") (pinfunction "RSVD_20") (pintype "passive+no_connect"))
    )
    (net (code "72") (name "unconnected-(IC9-RSVD-Pad21)") (class "Default")
      (node (ref "IC9") (pin "21") (pinfunction "RSVD_21") (pintype "passive+no_connect"))
    )
    (net (code "73") (name "unconnected-(IC9-RSVD-Pad55)") (class "Default")
      (node (ref "IC9") (pin "55") (pinfunction "RSVD_55") (pintype "passive+no_connect"))
    )
    (net (code "74") (name "unconnected-(IC9-RSVD-Pad56)") (class "Default")
      (node (ref "IC9") (pin "56") (pinfunction "RSVD_56") (pintype "passive+no_connect"))
    )
    (net (code "75") (name "unconnected-(IC9-VDDO0-Pad22)") (class "Default")
      (node (ref "IC9") (pin "22") (pinfunction "VDDO0_22") (pintype "power_in+no_connect"))
    )
    (net (code "76") (name "unconnected-(IC9-VDDO6-Pad43)") (class "Default")
      (node (ref "IC9") (pin "43") (pinfunction "VDDO6_43") (pintype "power_in+no_connect"))
    )
  )
)
